# schematic.net
KiCad netlist of a schematic drawn in EAGLE
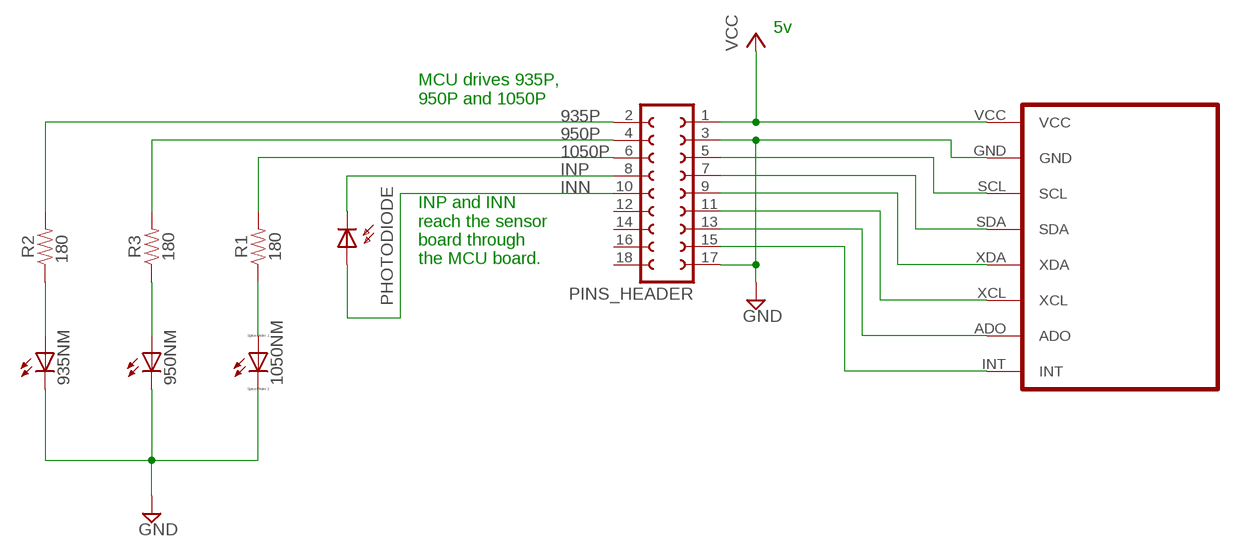
[diagram p0: schematic, sheet 1]

(export (version "E")
  (design (tool "Eeschema 10.0.6"))
  (components
    (comp (ref "935NM")
      (value "LEDIRL80A")
      (footprint "eagle-import:IRL80A")
      (libsource (lib "eagle-import") (part "LEDIRL80A"))
    )
    (comp (ref "950NM")
      (value "LEDIRL80A")
      (footprint "eagle-import:IRL80A")
      (libsource (lib "eagle-import") (part "LEDIRL80A"))
    )
    (comp (ref "1050NM")
      (value "LED_E")
      (footprint "eagle-import:LED_1206")
      (libsource (lib "eagle-import") (part "LED_E"))
    )
    (comp (ref "PHOTODIODE")
      (value "SFH206")
      (footprint "eagle-import:SFH206")
      (fields (field (name "MPN") "SFH206K"))
      (libsource (lib "eagle-import") (part "SFH206"))
    )
    (comp (ref "PINS_HEADER")
      (value "FE09-2")
      (footprint "eagle-import:FE09-2")
      (libsource (lib "eagle-import") (part "FE09-2"))
    )
    (comp (ref "R1")
      (value "180")
      (footprint "eagle-import:AXIAL-0.3")
      (libsource (lib "eagle-import") (part "RESISTORAXIAL-0.3"))
    )
    (comp (ref "R2")
      (value "180")
      (footprint "eagle-import:AXIAL-0.3")
      (libsource (lib "eagle-import") (part "RESISTORAXIAL-0.3"))
    )
    (comp (ref "R3")
      (value "180")
      (footprint "eagle-import:AXIAL-0.3")
      (libsource (lib "eagle-import") (part "RESISTORAXIAL-0.3"))
    )
    (comp (ref "U1")
      (value "GY-521MPU6050")
      (footprint "eagle-import:GY-521")
      (libsource (lib "eagle-import") (part "GY-521MPU6050"))
    )
  )
  (nets
    (net (code "1") (name "/935P") (class "Default")
      (node (ref "PINS_HEADER") (pin "2") (pinfunction "2_2") (pintype "passive"))
      (node (ref "R2") (pin "P$2") (pinfunction "2_P$2") (pintype "passive"))
    )
    (net (code "2") (name "/950P") (class "Default")
      (node (ref "PINS_HEADER") (pin "4") (pinfunction "4_4") (pintype "passive"))
      (node (ref "R3") (pin "P$2") (pinfunction "2_P$2") (pintype "passive"))
    )
    (net (code "3") (name "/1050P") (class "Default")
      (node (ref "PINS_HEADER") (pin "6") (pinfunction "6_6") (pintype "passive"))
      (node (ref "R1") (pin "P$2") (pinfunction "2_P$2") (pintype "passive"))
    )
    (net (code "4") (name "/INN") (class "Default")
      (node (ref "PHOTODIODE") (pin "A") (pinfunction "A_A") (pintype "passive"))
      (node (ref "PINS_HEADER") (pin "10") (pinfunction "10_10") (pintype "passive"))
    )
    (net (code "5") (name "/INP") (class "Default")
      (node (ref "PHOTODIODE") (pin "K") (pinfunction "C_K") (pintype "passive"))
      (node (ref "PINS_HEADER") (pin "8") (pinfunction "8_8") (pintype "passive"))
    )
    (net (code "6") (name "GND") (class "Default")
      (node (ref "1050NM") (pin "C") (pinfunction "C_C") (pintype "passive"))
      (node (ref "935NM") (pin "K") (pinfunction "C_K") (pintype "passive"))
      (node (ref "950NM") (pin "K") (pinfunction "C_K") (pintype "passive"))
      (node (ref "PINS_HEADER") (pin "17") (pinfunction "17_17") (pintype "passive"))
      (node (ref "PINS_HEADER") (pin "3") (pinfunction "3_3") (pintype "passive"))
      (node (ref "U1") (pin "GND") (pinfunction "GND_GND") (pintype "bidirectional"))
    )
    (net (code "7") (name "Net-(PINS_HEADER-Pad5)") (class "Default")
      (node (ref "PINS_HEADER") (pin "5") (pinfunction "5_5") (pintype "passive"))
      (node (ref "U1") (pin "SCL") (pinfunction "SCL_SCL") (pintype "bidirectional"))
    )
    (net (code "8") (name "Net-(PINS_HEADER-Pad7)") (class "Default")
      (node (ref "PINS_HEADER") (pin "7") (pinfunction "7_7") (pintype "passive"))
      (node (ref "U1") (pin "SDA") (pinfunction "SDA_SDA") (pintype "bidirectional"))
    )
    (net (code "9") (name "Net-(PINS_HEADER-Pad9)") (class "Default")
      (node (ref "PINS_HEADER") (pin "9") (pinfunction "9_9") (pintype "passive"))
      (node (ref "U1") (pin "XDA") (pinfunction "XDA_XDA") (pintype "bidirectional"))
    )
    (net (code "10") (name "Net-(PINS_HEADER-Pad11)") (class "Default")
      (node (ref "PINS_HEADER") (pin "11") (pinfunction "11_11") (pintype "passive"))
      (node (ref "U1") (pin "XCL") (pinfunction "XCL_XCL") (pintype "bidirectional"))
    )
    (net (code "11") (name "Net-(PINS_HEADER-Pad13)") (class "Default")
      (node (ref "PINS_HEADER") (pin "13") (pinfunction "13_13") (pintype "passive"))
      (node (ref "U1") (pin "ADO") (pinfunction "ADO_ADO") (pintype "bidirectional"))
    )
    (net (code "12") (name "Net-(PINS_HEADER-Pad15)") (class "Default")
      (node (ref "PINS_HEADER") (pin "15") (pinfunction "15_15") (pintype "passive"))
      (node (ref "U1") (pin "INT") (pinfunction "INT_INT") (pintype "bidirectional"))
    )
    (net (code "13") (name "Net-(R1-1)") (class "Default")
      (node (ref "1050NM") (pin "A") (pinfunction "A_A") (pintype "passive"))
      (node (ref "R1") (pin "P$1") (pinfunction "1_P$1") (pintype "passive"))
    )
    (net (code "14") (name "Net-(R2-1)") (class "Default")
      (node (ref "935NM") (pin "A") (pinfunction "A_A") (pintype "passive"))
      (node (ref "R2") (pin "P$1") (pinfunction "1_P$1") (pintype "passive"))
    )
    (net (code "15") (name "Net-(R3-1)") (class "Default")
      (node (ref "950NM") (pin "A") (pinfunction "A_A") (pintype "passive"))
      (node (ref "R3") (pin "P$1") (pinfunction "1_P$1") (pintype "passive"))
    )
    (net (code "16") (name "VCC") (class "Default")
      (node (ref "PINS_HEADER") (pin "1") (pinfunction "1_1") (pintype "passive"))
      (node (ref "U1") (pin "VCC") (pinfunction "VCC_VCC") (pintype "bidirectional"))
    )
    (net (code "17") (name "unconnected-(PINS_HEADER-Pad12)") (class "Default")
      (node (ref "PINS_HEADER") (pin "12") (pinfunction "12_12") (pintype "passive"))
    )
    (net (code "18") (name "unconnected-(PINS_HEADER-Pad14)") (class "Default")
      (node (ref "PINS_HEADER") (pin "14") (pinfunction "14_14") (pintype "passive"))
    )
    (net (code "19") (name "unconnected-(PINS_HEADER-Pad16)") (class "Default")
      (node (ref "PINS_HEADER") (pin "16") (pinfunction "16_16") (pintype "passive"))
    )
    (net (code "20") (name "unconnected-(PINS_HEADER-Pad18)") (class "Default")
      (node (ref "PINS_HEADER") (pin "18") (pinfunction "18_18") (pintype "passive"))
    )
  )
)
